# Ivy_Sensor_Shield.net
KiCad netlist of a schematic drawn in EAGLE
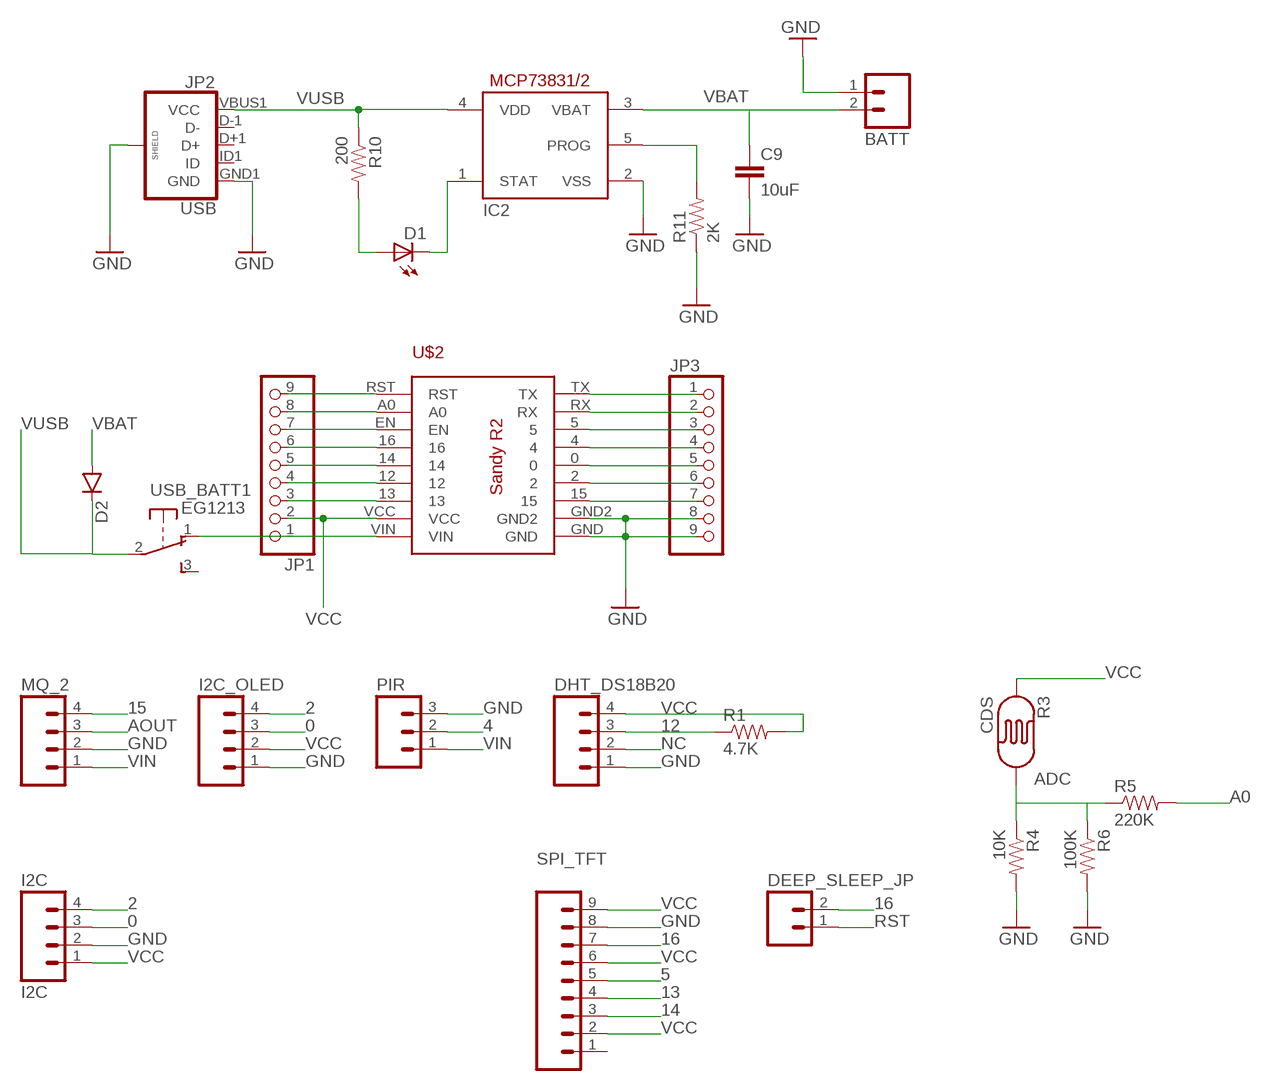
[diagram p0: schematic, sheet 1]

(export (version "E")
  (design (tool "Eeschema 10.0.6"))
  (components
    (comp (ref "BATT")
      (value "M02PTH")
      (footprint "eagle-import:1X02")
      (libsource (lib "eagle-import") (part "M02PTH"))
    )
    (comp (ref "C9")
      (value "10uF")
      (footprint "eagle-import:0805")
      (libsource (lib "eagle-import") (part "CAP0805"))
    )
    (comp (ref "D1")
      (value "LEDCHIPLED_0805")
      (footprint "eagle-import:CHIPLED_0805")
      (libsource (lib "eagle-import") (part "LEDCHIPLED_0805"))
    )
    (comp (ref "D2")
      (value "DIODESOD123")
      (footprint "eagle-import:SOD-123")
      (libsource (lib "eagle-import") (part "DIODESOD123"))
    )
    (comp (ref "DEEP_SLEEP_JP")
      (value "M02PTH")
      (footprint "eagle-import:1X02")
      (libsource (lib "eagle-import") (part "M02PTH"))
    )
    (comp (ref "DHT_DS18B20")
      (value "M04PTH")
      (footprint "eagle-import:1X04")
      (libsource (lib "eagle-import") (part "M04PTH"))
    )
    (comp (ref "I2C")
      (value "I2C")
      (footprint "eagle-import:1X04")
      (libsource (lib "eagle-import") (part "M04PTH"))
    )
    (comp (ref "I2C_OLED")
      (value "M04PTH")
      (footprint "eagle-import:1X04")
      (libsource (lib "eagle-import") (part "M04PTH"))
    )
    (comp (ref "IC2")
      (value "MCP73831/OT")
      (footprint "eagle-import:SOT23-5L")
      (libsource (lib "eagle-import") (part "MCP73831/OT"))
    )
    (comp (ref "JP1")
      (value "PINHD-1X9")
      (footprint "eagle-import:1X09-BIG")
      (libsource (lib "eagle-import") (part "PINHD-1X9"))
    )
    (comp (ref "JP2")
      (value "USB")
      (footprint "eagle-import:USB-B-MICRO-SMD_V03")
      (libsource (lib "eagle-import") (part "USB_MICROB_PLUGCONN-11752"))
    )
    (comp (ref "JP3")
      (value "PINHD-1X9")
      (footprint "eagle-import:1X09-BIG")
      (libsource (lib "eagle-import") (part "PINHD-1X9"))
    )
    (comp (ref "MQ_2")
      (value "M04PTH")
      (footprint "eagle-import:1X04")
      (libsource (lib "eagle-import") (part "M04PTH"))
    )
    (comp (ref "PIR")
      (value "M03PTH")
      (footprint "eagle-import:1X03")
      (libsource (lib "eagle-import") (part "M03PTH"))
    )
    (comp (ref "R1")
      (value "4.7K")
      (footprint "eagle-import:0805")
      (libsource (lib "eagle-import") (part "RESISTOR0805-RES"))
    )
    (comp (ref "R3")
      (value "CDS")
      (footprint "eagle-import:PHOTOCELL_THIN")
      (libsource (lib "eagle-import") (part "PHOTOCELL"))
    )
    (comp (ref "R4")
      (value "10K")
      (footprint "eagle-import:0805")
      (libsource (lib "eagle-import") (part "RESISTOR0805-RES"))
    )
    (comp (ref "R5")
      (value "220K")
      (footprint "eagle-import:0805")
      (libsource (lib "eagle-import") (part "RESISTOR0805-RES"))
    )
    (comp (ref "R6")
      (value "100K")
      (footprint "eagle-import:0805")
      (libsource (lib "eagle-import") (part "RESISTOR0805-RES"))
    )
    (comp (ref "R10")
      (value "200")
      (footprint "eagle-import:0805")
      (libsource (lib "eagle-import") (part "RESISTOR0805-RES"))
    )
    (comp (ref "R11")
      (value "2K")
      (footprint "eagle-import:0805")
      (libsource (lib "eagle-import") (part "RESISTOR0805-RES"))
    )
    (comp (ref "SPI_TFT")
      (value "M09")
      (footprint "eagle-import:1X09")
      (libsource (lib "eagle-import") (part "M09"))
    )
    (comp (ref "U$2")
      (value "MINI-ESPMINI-ESP-LOCK")
      (footprint "eagle-import:MINI-ESP-LOCK")
      (libsource (lib "eagle-import") (part "MINI-ESPMINI-ESP-LOCK"))
    )
    (comp (ref "USB_BATT")
      (value "EG1213")
      (footprint "eagle-import:EG1213")
      (libsource (lib "eagle-import") (part "EG1213"))
    )
  )
  (nets
    (net (code "1") (name "/0") (class "Default")
      (node (ref "I2C") (pin "3") (pinfunction "3_3") (pintype "passive"))
      (node (ref "I2C_OLED") (pin "3") (pinfunction "3_3") (pintype "passive"))
      (node (ref "JP3") (pin "5") (pinfunction "5_5") (pintype "passive"))
      (node (ref "U$2") (pin "0") (pinfunction "0_0") (pintype "bidirectional"))
    )
    (net (code "2") (name "/2") (class "Default")
      (node (ref "I2C") (pin "4") (pinfunction "4_4") (pintype "passive"))
      (node (ref "I2C_OLED") (pin "4") (pinfunction "4_4") (pintype "passive"))
      (node (ref "JP3") (pin "6") (pinfunction "6_6") (pintype "passive"))
      (node (ref "U$2") (pin "2") (pinfunction "2_2") (pintype "bidirectional"))
    )
    (net (code "3") (name "/4") (class "Default")
      (node (ref "JP3") (pin "4") (pinfunction "4_4") (pintype "passive"))
      (node (ref "PIR") (pin "2") (pinfunction "2_2") (pintype "passive"))
      (node (ref "U$2") (pin "4") (pinfunction "4_4") (pintype "bidirectional"))
    )
    (net (code "4") (name "/5") (class "Default")
      (node (ref "JP3") (pin "3") (pinfunction "3_3") (pintype "passive"))
      (node (ref "SPI_TFT") (pin "5") (pinfunction "5_5") (pintype "passive"))
      (node (ref "U$2") (pin "5") (pinfunction "5_5") (pintype "bidirectional"))
    )
    (net (code "5") (name "/12") (class "Default")
      (node (ref "DHT_DS18B20") (pin "3") (pinfunction "3_3") (pintype "passive"))
      (node (ref "JP1") (pin "4") (pinfunction "4_4") (pintype "passive"))
      (node (ref "R1") (pin "1") (pinfunction "1_1") (pintype "passive"))
      (node (ref "U$2") (pin "12") (pinfunction "12_12") (pintype "bidirectional"))
    )
    (net (code "6") (name "/13") (class "Default")
      (node (ref "JP1") (pin "3") (pinfunction "3_3") (pintype "passive"))
      (node (ref "SPI_TFT") (pin "4") (pinfunction "4_4") (pintype "passive"))
      (node (ref "U$2") (pin "13") (pinfunction "13_13") (pintype "bidirectional"))
    )
    (net (code "7") (name "/14") (class "Default")
      (node (ref "JP1") (pin "5") (pinfunction "5_5") (pintype "passive"))
      (node (ref "SPI_TFT") (pin "3") (pinfunction "3_3") (pintype "passive"))
      (node (ref "U$2") (pin "14") (pinfunction "14_14") (pintype "bidirectional"))
    )
    (net (code "8") (name "/15") (class "Default")
      (node (ref "JP3") (pin "7") (pinfunction "7_7") (pintype "passive"))
      (node (ref "MQ_2") (pin "4") (pinfunction "4_4") (pintype "passive"))
      (node (ref "U$2") (pin "15") (pinfunction "15_15") (pintype "bidirectional"))
    )
    (net (code "9") (name "/16") (class "Default")
      (node (ref "DEEP_SLEEP_JP") (pin "2") (pinfunction "2_2") (pintype "passive"))
      (node (ref "JP1") (pin "6") (pinfunction "6_6") (pintype "passive"))
      (node (ref "SPI_TFT") (pin "7") (pinfunction "7_7") (pintype "passive"))
      (node (ref "U$2") (pin "16") (pinfunction "16_16") (pintype "bidirectional"))
    )
    (net (code "10") (name "/A0") (class "Default")
      (node (ref "JP1") (pin "8") (pinfunction "8_8") (pintype "passive"))
      (node (ref "R5") (pin "2") (pinfunction "2_2") (pintype "passive"))
      (node (ref "U$2") (pin "A0") (pinfunction "A0_A0") (pintype "bidirectional"))
    )
    (net (code "11") (name "/ADC") (class "Default")
      (node (ref "R3") (pin "2") (pinfunction "P$2_2") (pintype "bidirectional"))
      (node (ref "R4") (pin "1") (pinfunction "1_1") (pintype "passive"))
      (node (ref "R5") (pin "1") (pinfunction "1_1") (pintype "passive"))
      (node (ref "R6") (pin "1") (pinfunction "1_1") (pintype "passive"))
    )
    (net (code "12") (name "/AOUT") (class "Default")
      (node (ref "MQ_2") (pin "3") (pinfunction "3_3") (pintype "passive"))
    )
    (net (code "13") (name "/NC") (class "Default")
      (node (ref "DHT_DS18B20") (pin "2") (pinfunction "2_2") (pintype "passive"))
    )
    (net (code "14") (name "/RST") (class "Default")
      (node (ref "DEEP_SLEEP_JP") (pin "1") (pinfunction "1_1") (pintype "passive"))
      (node (ref "JP1") (pin "9") (pinfunction "9_9") (pintype "passive"))
      (node (ref "U$2") (pin "RST") (pinfunction "RST_RST") (pintype "bidirectional"))
    )
    (net (code "15") (name "/VBAT") (class "Default")
      (node (ref "BATT") (pin "2") (pinfunction "2_2") (pintype "passive"))
      (node (ref "C9") (pin "1") (pinfunction "1_1") (pintype "passive"))
      (node (ref "D2") (pin "A") (pinfunction "A_A") (pintype "passive"))
      (node (ref "IC2") (pin "3") (pinfunction "VBAT_3") (pintype "bidirectional"))
    )
    (net (code "16") (name "/VCC") (class "Default")
      (node (ref "DHT_DS18B20") (pin "4") (pinfunction "4_4") (pintype "passive"))
      (node (ref "I2C") (pin "1") (pinfunction "1_1") (pintype "passive"))
      (node (ref "I2C_OLED") (pin "2") (pinfunction "2_2") (pintype "passive"))
      (node (ref "JP1") (pin "2") (pinfunction "2_2") (pintype "passive"))
      (node (ref "R1") (pin "2") (pinfunction "2_2") (pintype "passive"))
      (node (ref "R3") (pin "1") (pinfunction "P$1_1") (pintype "bidirectional"))
      (node (ref "SPI_TFT") (pin "2") (pinfunction "2_2") (pintype "passive"))
      (node (ref "SPI_TFT") (pin "6") (pinfunction "6_6") (pintype "passive"))
      (node (ref "SPI_TFT") (pin "9") (pinfunction "9_9") (pintype "passive"))
      (node (ref "U$2") (pin "VCC") (pinfunction "VCC_VCC") (pintype "bidirectional"))
    )
    (net (code "17") (name "/VIN") (class "Default")
      (node (ref "JP1") (pin "1") (pinfunction "1_1") (pintype "passive"))
      (node (ref "MQ_2") (pin "1") (pinfunction "1_1") (pintype "passive"))
      (node (ref "PIR") (pin "1") (pinfunction "1_1") (pintype "passive"))
      (node (ref "U$2") (pin "VIN") (pinfunction "VIN_VIN") (pintype "bidirectional"))
      (node (ref "USB_BATT") (pin "1") (pinfunction "O_1") (pintype "passive"))
    )
    (net (code "18") (name "/VUSB") (class "Default")
      (node (ref "D2") (pin "C") (pinfunction "C_C") (pintype "passive"))
      (node (ref "IC2") (pin "4") (pinfunction "VDD_4") (pintype "power_in"))
      (node (ref "JP2") (pin "VBUS1") (pinfunction "VCC_VBUS1") (pintype "bidirectional"))
      (node (ref "R10") (pin "1") (pinfunction "1_1") (pintype "passive"))
      (node (ref "USB_BATT") (pin "2") (pinfunction "P_2") (pintype "passive"))
    )
    (net (code "19") (name "GND") (class "Default")
      (node (ref "BATT") (pin "1") (pinfunction "1_1") (pintype "passive"))
      (node (ref "C9") (pin "2") (pinfunction "2_2") (pintype "passive"))
      (node (ref "DHT_DS18B20") (pin "1") (pinfunction "1_1") (pintype "passive"))
      (node (ref "I2C") (pin "2") (pinfunction "2_2") (pintype "passive"))
      (node (ref "I2C_OLED") (pin "1") (pinfunction "1_1") (pintype "passive"))
      (node (ref "IC2") (pin "2") (pinfunction "VSS_2") (pintype "power_in"))
      (node (ref "JP2") (pin "GND1") (pinfunction "GND_GND1") (pintype "bidirectional"))
      (node (ref "JP2") (pin "SHIELD1") (pinfunction "SHIELD_SHIELD1") (pintype "bidirectional"))
      (node (ref "JP2") (pin "SHIELD2") (pinfunction "SHIELD_SHIELD2") (pintype "bidirectional"))
      (node (ref "JP2") (pin "SHIELD3") (pinfunction "SHIELD_SHIELD3") (pintype "bidirectional"))
      (node (ref "JP3") (pin "8") (pinfunction "8_8") (pintype "passive"))
      (node (ref "JP3") (pin "9") (pinfunction "9_9") (pintype "passive"))
      (node (ref "MQ_2") (pin "2") (pinfunction "2_2") (pintype "passive"))
      (node (ref "PIR") (pin "3") (pinfunction "3_3") (pintype "passive"))
      (node (ref "R11") (pin "1") (pinfunction "1_1") (pintype "passive"))
      (node (ref "R4") (pin "2") (pinfunction "2_2") (pintype "passive"))
      (node (ref "R6") (pin "2") (pinfunction "2_2") (pintype "passive"))
      (node (ref "SPI_TFT") (pin "8") (pinfunction "8_8") (pintype "passive"))
      (node (ref "U$2") (pin "GND") (pinfunction "GND_GND") (pintype "bidirectional"))
      (node (ref "U$2") (pin "GND2") (pinfunction "GND2_GND2") (pintype "bidirectional"))
    )
    (net (code "20") (name "Net-(D1-PadA)") (class "Default")
      (node (ref "D1") (pin "A") (pinfunction "A_A") (pintype "passive"))
      (node (ref "R10") (pin "2") (pinfunction "2_2") (pintype "passive"))
    )
    (net (code "21") (name "Net-(IC2-PROG)") (class "Default")
      (node (ref "IC2") (pin "5") (pinfunction "PROG_5") (pintype "input"))
      (node (ref "R11") (pin "2") (pinfunction "2_2") (pintype "passive"))
    )
    (net (code "22") (name "Net-(IC2-STAT)") (class "Default")
      (node (ref "D1") (pin "C") (pinfunction "C_C") (pintype "passive"))
      (node (ref "IC2") (pin "1") (pinfunction "STAT_1") (pintype "output"))
    )
    (net (code "23") (name "Net-(JP1-Pad7)") (class "Default")
      (node (ref "JP1") (pin "7") (pinfunction "7_7") (pintype "passive"))
      (node (ref "U$2") (pin "EN") (pinfunction "EN_EN") (pintype "bidirectional"))
    )
    (net (code "24") (name "Net-(JP3-Pad1)") (class "Default")
      (node (ref "JP3") (pin "1") (pinfunction "1_1") (pintype "passive"))
      (node (ref "U$2") (pin "TX") (pinfunction "TX_TX") (pintype "bidirectional"))
    )
    (net (code "25") (name "Net-(JP3-Pad2)") (class "Default")
      (node (ref "JP3") (pin "2") (pinfunction "2_2") (pintype "passive"))
      (node (ref "U$2") (pin "RX") (pinfunction "RX_RX") (pintype "bidirectional"))
    )
    (net (code "26") (name "unconnected-(JP2-D+-PadD+1)") (class "Default")
      (node (ref "JP2") (pin "D+1") (pinfunction "D+_D+1") (pintype "bidirectional"))
    )
    (net (code "27") (name "unconnected-(JP2-D--PadD-1)") (class "Default")
      (node (ref "JP2") (pin "D-1") (pinfunction "D-_D-1") (pintype "bidirectional"))
    )
    (net (code "28") (name "unconnected-(JP2-ID-PadID1)") (class "Default")
      (node (ref "JP2") (pin "ID1") (pinfunction "ID_ID1") (pintype "bidirectional"))
    )
    (net (code "29") (name "unconnected-(SPI_TFT-Pad1)") (class "Default")
      (node (ref "SPI_TFT") (pin "1") (pinfunction "1_1") (pintype "passive"))
    )
    (net (code "30") (name "unconnected-(USB_BATTA-S-Pad3)") (class "Default")
      (node (ref "USB_BATT") (pin "3") (pinfunction "S_3") (pintype "passive"))
    )
  )
)
